# 16SegBoard_AutoRoute.net
KiCad netlist of a schematic drawn in EAGLE
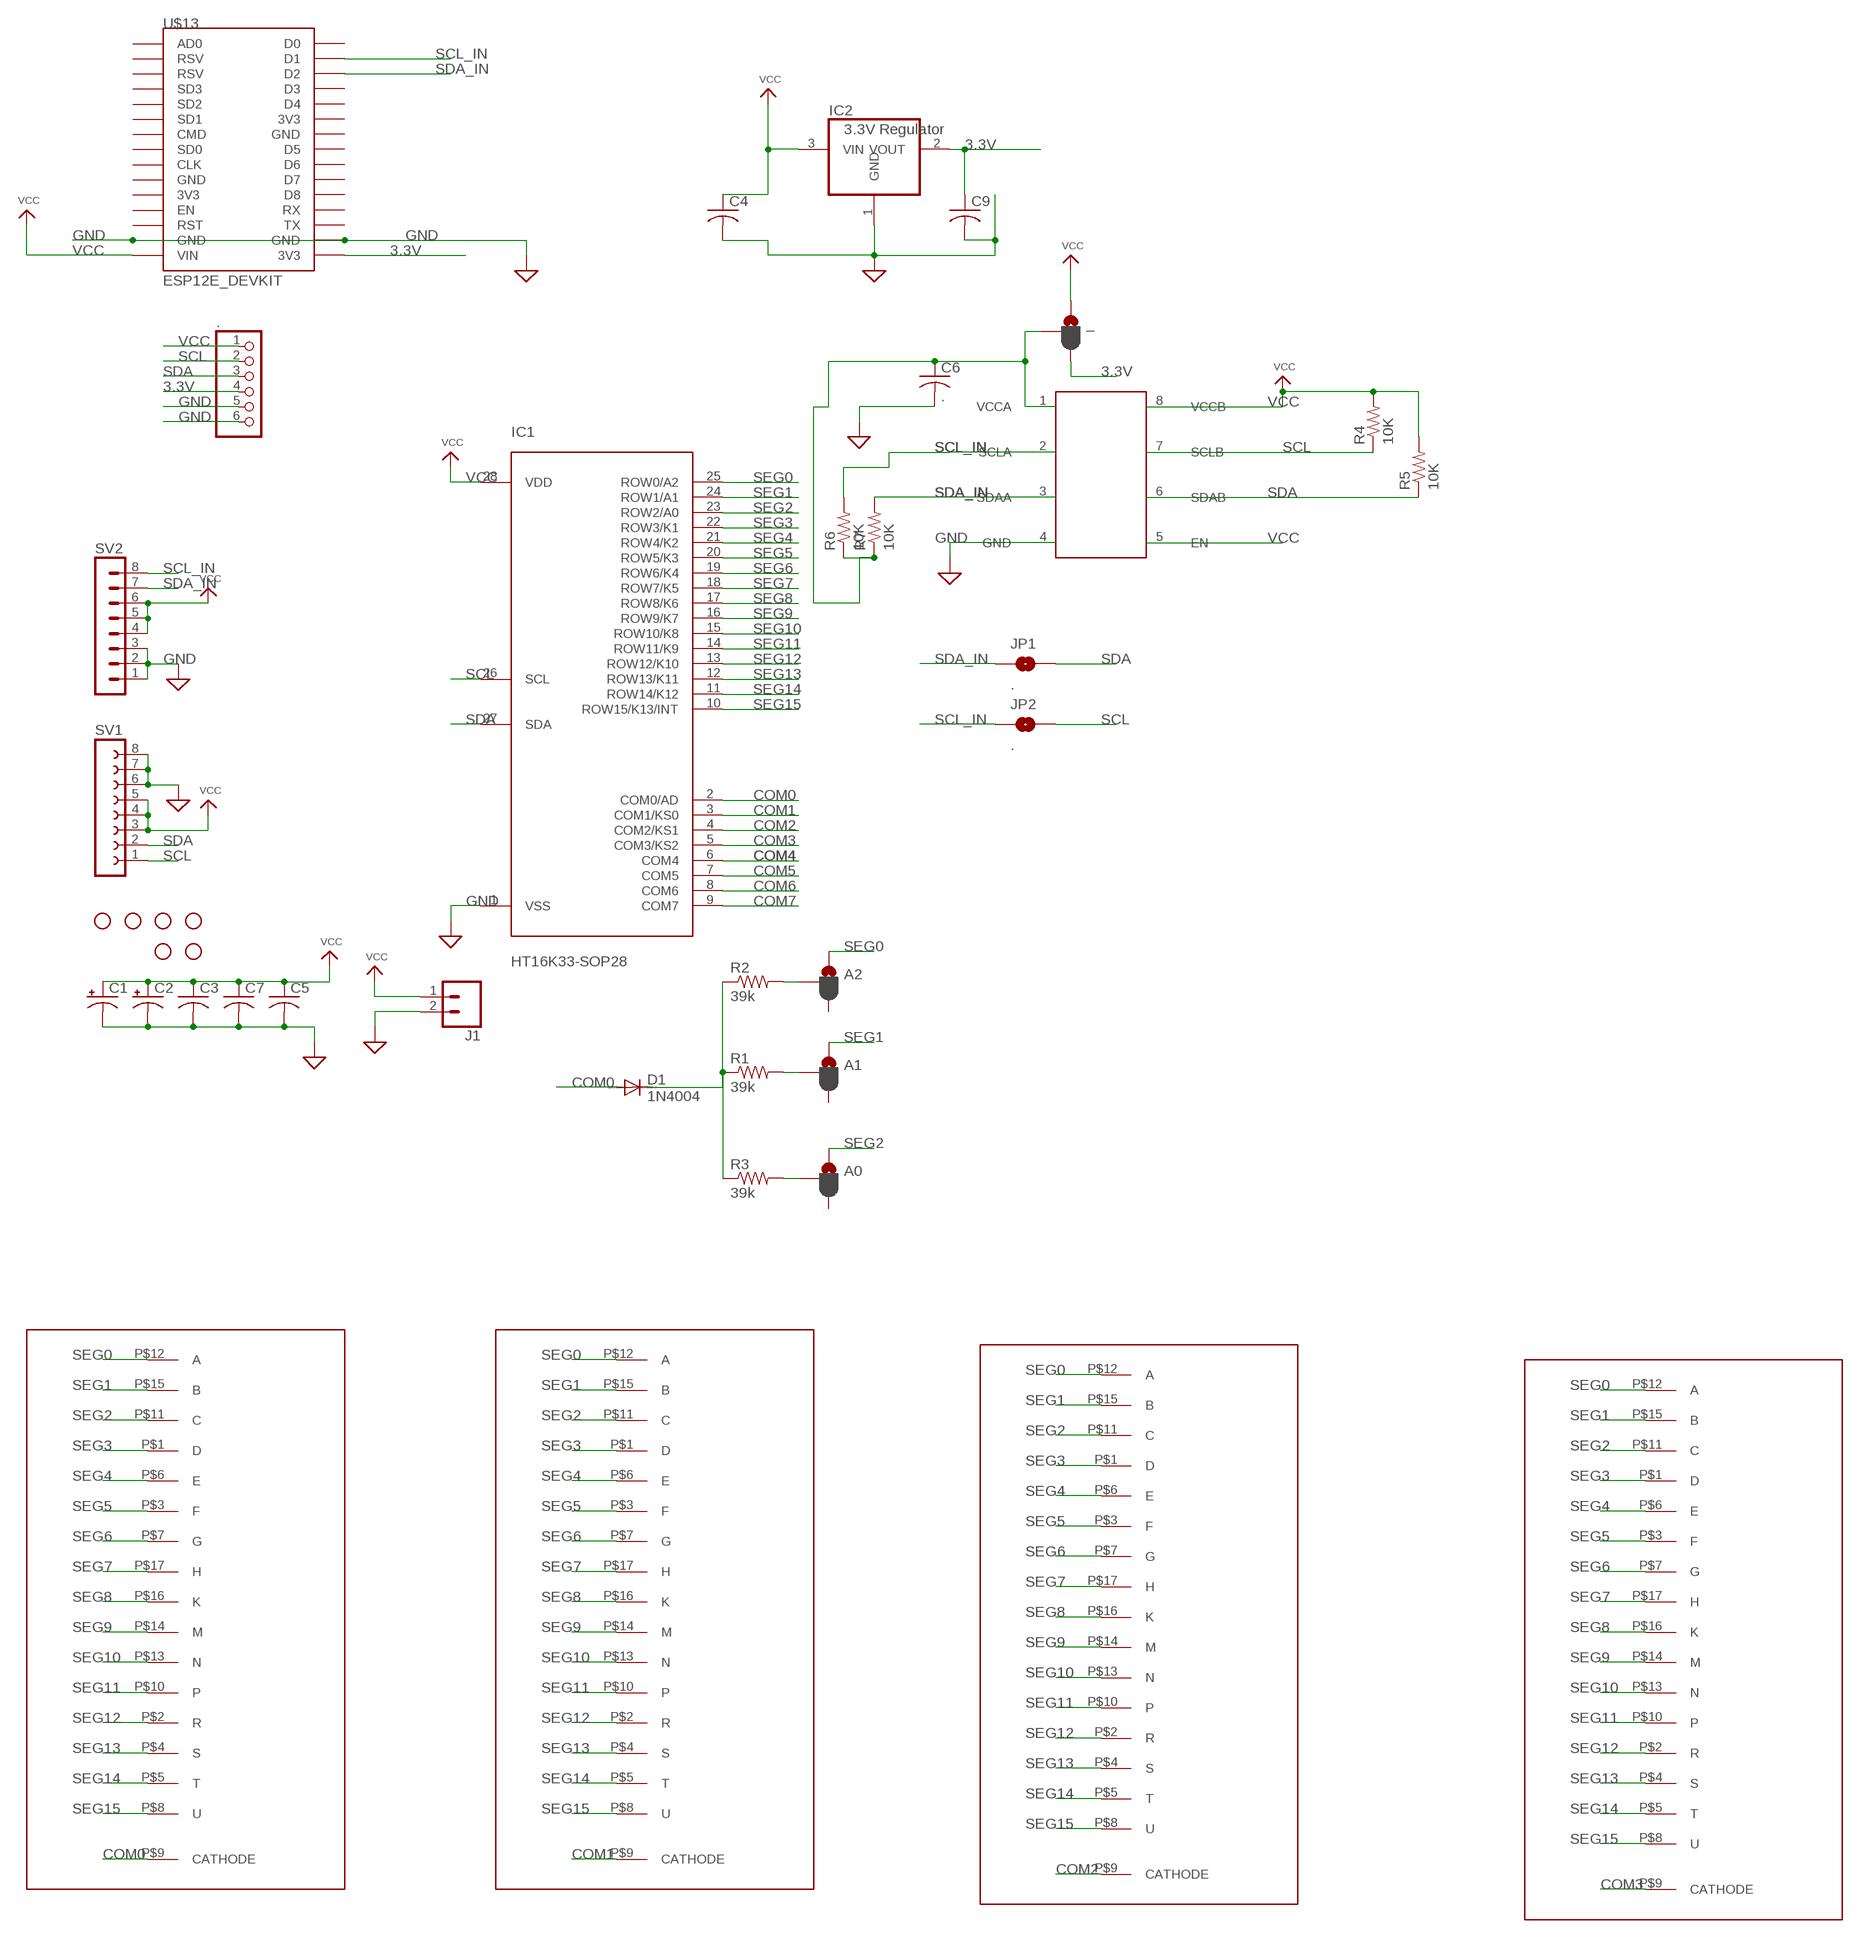
[diagram p0: schematic, sheet 1, part 1 of 2]
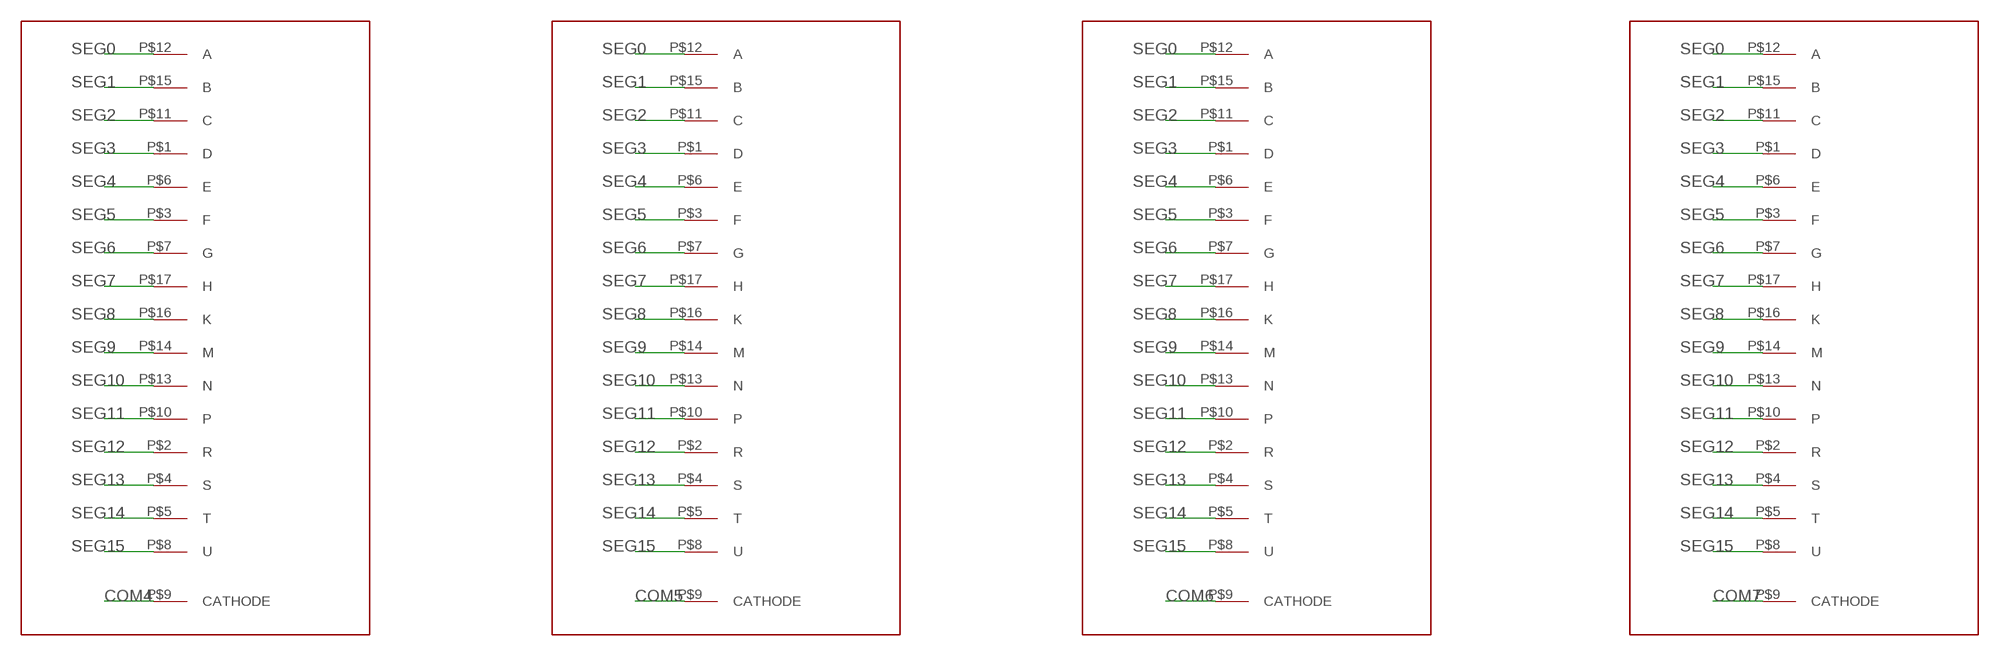
[diagram p1: schematic, sheet 1, part 2 of 2]

(export (version "E")
  (design (tool "Eeschema 10.0.6"))
  (components
    (comp (ref ".")
      (value "PINHD-1X6")
      (footprint "eagle-import:1X06")
      (libsource (lib "eagle-import") (part "PINHD-1X6"))
    )
    (comp (ref "A0")
      (value "JUMPER-SMT_3_1-NC_PASTE_SILK")
      (footprint "eagle-import:SMT-JUMPER_3_1-NC_PASTE_SILK")
      (libsource (lib "eagle-import") (part "JUMPER-SMT_3_1-NC_PASTE_SILK"))
    )
    (comp (ref "A1")
      (value "JUMPER-SMT_3_1-NC_PASTE_SILK")
      (footprint "eagle-import:SMT-JUMPER_3_1-NC_PASTE_SILK")
      (libsource (lib "eagle-import") (part "JUMPER-SMT_3_1-NC_PASTE_SILK"))
    )
    (comp (ref "A2")
      (value "JUMPER-SMT_3_1-NC_PASTE_SILK")
      (footprint "eagle-import:SMT-JUMPER_3_1-NC_PASTE_SILK")
      (libsource (lib "eagle-import") (part "JUMPER-SMT_3_1-NC_PASTE_SILK"))
    )
    (comp (ref "C1")
      (value "CPOL-USE2.5-6")
      (footprint "eagle-import:E2,5-6")
      (libsource (lib "eagle-import") (part "CPOL-USE2.5-6"))
    )
    (comp (ref "C2")
      (value "CPOL-USE2.5-6")
      (footprint "eagle-import:E2,5-6")
      (libsource (lib "eagle-import") (part "CPOL-USE2.5-6"))
    )
    (comp (ref "C3")
      (value "C-USC0805")
      (footprint "eagle-import:C0805")
      (libsource (lib "eagle-import") (part "C-USC0805"))
    )
    (comp (ref "C4")
      (value "C-USC0805")
      (footprint "eagle-import:C0805")
      (libsource (lib "eagle-import") (part "C-USC0805"))
    )
    (comp (ref "C5")
      (value "C-US025-030X050")
      (footprint "eagle-import:C025-030X050")
      (libsource (lib "eagle-import") (part "C-US025-030X050"))
    )
    (comp (ref "C6")
      (value ".")
      (footprint "eagle-import:C0805")
      (libsource (lib "eagle-import") (part "C-USC0805"))
    )
    (comp (ref "C7")
      (value "C-USC0805")
      (footprint "eagle-import:C0805")
      (libsource (lib "eagle-import") (part "C-USC0805"))
    )
    (comp (ref "C9")
      (value "C-USC0805")
      (footprint "eagle-import:C0805")
      (libsource (lib "eagle-import") (part "C-USC0805"))
    )
    (comp (ref "D1")
      (value "1N4004")
      (footprint "eagle-import:DO41-10")
      (libsource (lib "eagle-import") (part "1N4004"))
    )
    (comp (ref "H1")
      (value "STAND-OFF")
      (footprint "eagle-import:STAND-OFF")
      (libsource (lib "eagle-import") (part "STAND-OFF"))
    )
    (comp (ref "H2")
      (value "STAND-OFF")
      (footprint "eagle-import:STAND-OFF")
      (libsource (lib "eagle-import") (part "STAND-OFF"))
    )
    (comp (ref "H3")
      (value "STAND-OFF")
      (footprint "eagle-import:STAND-OFF")
      (libsource (lib "eagle-import") (part "STAND-OFF"))
    )
    (comp (ref "H4")
      (value "STAND-OFF")
      (footprint "eagle-import:STAND-OFF")
      (libsource (lib "eagle-import") (part "STAND-OFF"))
    )
    (comp (ref "H5")
      (value "STAND-OFF")
      (footprint "eagle-import:STAND-OFF")
      (libsource (lib "eagle-import") (part "STAND-OFF"))
    )
    (comp (ref "H6")
      (value "STAND-OFF")
      (footprint "eagle-import:STAND-OFF")
      (libsource (lib "eagle-import") (part "STAND-OFF"))
    )
    (comp (ref "IC1")
      (value "HT16K33-SOP28")
      (footprint "eagle-import:SOIC127P1031X264-28N")
      (libsource (lib "eagle-import") (part "HT16K33-SOP28"))
    )
    (comp (ref "IC2")
      (value "3.3V Regulator")
      (footprint "eagle-import:SOT223")
      (fields (field (name "MPN") "REG1117"))
      (libsource (lib "eagle-import") (part "REG1117"))
    )
    (comp (ref "J1")
      (value "CONN_025MM")
      (footprint "eagle-import:SCREWTERMINAL-5MM-2")
      (libsource (lib "eagle-import") (part "CONN_025MM"))
    )
    (comp (ref "JP1")
      (value ".")
      (footprint "eagle-import:SMT-JUMPER_2_NO_NO-SILK")
      (libsource (lib "eagle-import") (part "JUMPER-SMT_2_NO_NO-SILK"))
    )
    (comp (ref "JP2")
      (value ".")
      (footprint "eagle-import:SMT-JUMPER_2_NO_NO-SILK")
      (libsource (lib "eagle-import") (part "JUMPER-SMT_2_NO_NO-SILK"))
    )
    (comp (ref "R1")
      (value "39k")
      (footprint "eagle-import:M1206")
      (libsource (lib "eagle-import") (part "R-US_M1206"))
    )
    (comp (ref "R2")
      (value "39k")
      (footprint "eagle-import:M1206")
      (libsource (lib "eagle-import") (part "R-US_M1206"))
    )
    (comp (ref "R3")
      (value "39k")
      (footprint "eagle-import:M1206")
      (libsource (lib "eagle-import") (part "R-US_M1206"))
    )
    (comp (ref "R4")
      (value "10K")
      (footprint "eagle-import:R1206")
      (libsource (lib "eagle-import") (part "R-US_R1206"))
    )
    (comp (ref "R5")
      (value "10K")
      (footprint "eagle-import:R1206")
      (libsource (lib "eagle-import") (part "R-US_R1206"))
    )
    (comp (ref "R6")
      (value "10K")
      (footprint "eagle-import:R1206")
      (libsource (lib "eagle-import") (part "R-US_R1206"))
    )
    (comp (ref "R7")
      (value "10K")
      (footprint "eagle-import:R1206")
      (libsource (lib "eagle-import") (part "R-US_R1206"))
    )
    (comp (ref "SV1")
      (value "FE08W")
      (footprint "eagle-import:FE08W")
      (libsource (lib "eagle-import") (part "FE08W"))
    )
    (comp (ref "SV2")
      (value "MA08-1W")
      (footprint "eagle-import:MA08-1W")
      (libsource (lib "eagle-import") (part "MA08-1W"))
    )
    (comp (ref "TCA9517")
      (value "TCA9517")
      (footprint "eagle-import:SOIC-8")
      (libsource (lib "eagle-import") (part "TCA9517"))
    )
    (comp (ref "U$1")
      (value "16SEG")
      (footprint "eagle-import:16SEGLARGE_PKG")
      (libsource (lib "eagle-import") (part "16SEG"))
    )
    (comp (ref "U$2")
      (value "16SEG")
      (footprint "eagle-import:16SEGLARGE_PKG")
      (libsource (lib "eagle-import") (part "16SEG"))
    )
    (comp (ref "U$3")
      (value "16SEG")
      (footprint "eagle-import:16SEGLARGE_PKG")
      (libsource (lib "eagle-import") (part "16SEG"))
    )
    (comp (ref "U$4")
      (value "16SEG")
      (footprint "eagle-import:16SEGLARGE_PKG")
      (libsource (lib "eagle-import") (part "16SEG"))
    )
    (comp (ref "U$5")
      (value "16SEG")
      (footprint "eagle-import:16SEGLARGE_PKG")
      (libsource (lib "eagle-import") (part "16SEG"))
    )
    (comp (ref "U$6")
      (value "16SEG")
      (footprint "eagle-import:16SEGLARGE_PKG")
      (libsource (lib "eagle-import") (part "16SEG"))
    )
    (comp (ref "U$7")
      (value "16SEG")
      (footprint "eagle-import:16SEGLARGE_PKG")
      (libsource (lib "eagle-import") (part "16SEG"))
    )
    (comp (ref "U$8")
      (value "16SEG")
      (footprint "eagle-import:16SEGLARGE_PKG")
      (libsource (lib "eagle-import") (part "16SEG"))
    )
    (comp (ref "U$13")
      (value "ESP12E_DEVKIT")
      (footprint "eagle-import:ESP12E_DEVKIT")
      (libsource (lib "eagle-import") (part "ESP12E_DEVKIT"))
    )
    (comp (ref "_")
      (value "JUMPER-SMT_3_1-NC_PASTE_SILK")
      (footprint "eagle-import:SMT-JUMPER_3_1-NC_PASTE_SILK")
      (libsource (lib "eagle-import") (part "JUMPER-SMT_3_1-NC_PASTE_SILK"))
    )
  )
  (nets
    (net (code "1") (name "/3.3V") (class "Default")
      (node (ref ".") (pin "4") (pinfunction "4_4") (pintype "passive"))
      (node (ref "C9") (pin "1") (pinfunction "1_1") (pintype "passive"))
      (node (ref "IC2") (pin "2") (pinfunction "VOUT_2") (pintype "output"))
      (node (ref "U$13") (pin "3V3@2") (pinfunction "3V3_3V3@2") (pintype "bidirectional"))
      (node (ref "_") (pin "3") (pinfunction "3_3") (pintype "passive"))
    )
    (net (code "2") (name "/COM0") (class "Default")
      (node (ref "D1") (pin "A") (pinfunction "A_A") (pintype "passive"))
      (node (ref "IC1") (pin "2") (pinfunction "COM0/AD_2") (pintype "output"))
      (node (ref "U$1") (pin "P$9") (pinfunction "CATHODE_P$9") (pintype "bidirectional"))
    )
    (net (code "3") (name "/COM1") (class "Default")
      (node (ref "IC1") (pin "3") (pinfunction "COM1/KS0_3") (pintype "output"))
      (node (ref "U$2") (pin "P$9") (pinfunction "CATHODE_P$9") (pintype "bidirectional"))
    )
    (net (code "4") (name "/COM2") (class "Default")
      (node (ref "IC1") (pin "4") (pinfunction "COM2/KS1_4") (pintype "output"))
      (node (ref "U$3") (pin "P$9") (pinfunction "CATHODE_P$9") (pintype "bidirectional"))
    )
    (net (code "5") (name "/COM3") (class "Default")
      (node (ref "IC1") (pin "5") (pinfunction "COM3/KS2_5") (pintype "output"))
      (node (ref "U$4") (pin "P$9") (pinfunction "CATHODE_P$9") (pintype "bidirectional"))
    )
    (net (code "6") (name "/COM4") (class "Default")
      (node (ref "IC1") (pin "6") (pinfunction "COM4_6") (pintype "output"))
      (node (ref "U$5") (pin "P$9") (pinfunction "CATHODE_P$9") (pintype "bidirectional"))
    )
    (net (code "7") (name "/COM5") (class "Default")
      (node (ref "IC1") (pin "7") (pinfunction "COM5_7") (pintype "output"))
      (node (ref "U$6") (pin "P$9") (pinfunction "CATHODE_P$9") (pintype "bidirectional"))
    )
    (net (code "8") (name "/COM6") (class "Default")
      (node (ref "IC1") (pin "8") (pinfunction "COM6_8") (pintype "output"))
      (node (ref "U$7") (pin "P$9") (pinfunction "CATHODE_P$9") (pintype "bidirectional"))
    )
    (net (code "9") (name "/COM7") (class "Default")
      (node (ref "IC1") (pin "9") (pinfunction "COM7_9") (pintype "output"))
      (node (ref "U$8") (pin "P$9") (pinfunction "CATHODE_P$9") (pintype "bidirectional"))
    )
    (net (code "10") (name "/SCL") (class "Default")
      (node (ref ".") (pin "2") (pinfunction "2_2") (pintype "passive"))
      (node (ref "IC1") (pin "26") (pinfunction "SCL_26") (pintype "input"))
      (node (ref "JP2") (pin "2") (pinfunction "2_2") (pintype "passive"))
      (node (ref "R4") (pin "1") (pinfunction "1_1") (pintype "passive"))
      (node (ref "SV1") (pin "1") (pinfunction "1_1") (pintype "passive"))
      (node (ref "TCA9517") (pin "7") (pinfunction "SCLB_7") (pintype "bidirectional"))
    )
    (net (code "11") (name "/SCL_IN") (class "Default")
      (node (ref "JP2") (pin "1") (pinfunction "1_1") (pintype "passive"))
      (node (ref "R6") (pin "2") (pinfunction "2_2") (pintype "passive"))
      (node (ref "SV2") (pin "8") (pinfunction "8_8") (pintype "passive"))
      (node (ref "TCA9517") (pin "2") (pinfunction "SCLA_2") (pintype "bidirectional"))
      (node (ref "U$13") (pin "D1") (pinfunction "D1_D1") (pintype "bidirectional"))
    )
    (net (code "12") (name "/SDA") (class "Default")
      (node (ref ".") (pin "3") (pinfunction "3_3") (pintype "passive"))
      (node (ref "IC1") (pin "27") (pinfunction "SDA_27") (pintype "bidirectional"))
      (node (ref "JP1") (pin "2") (pinfunction "2_2") (pintype "passive"))
      (node (ref "R5") (pin "1") (pinfunction "1_1") (pintype "passive"))
      (node (ref "SV1") (pin "2") (pinfunction "2_2") (pintype "passive"))
      (node (ref "TCA9517") (pin "6") (pinfunction "SDAB_6") (pintype "bidirectional"))
    )
    (net (code "13") (name "/SDA_IN") (class "Default")
      (node (ref "JP1") (pin "1") (pinfunction "1_1") (pintype "passive"))
      (node (ref "R7") (pin "2") (pinfunction "2_2") (pintype "passive"))
      (node (ref "SV2") (pin "7") (pinfunction "7_7") (pintype "passive"))
      (node (ref "TCA9517") (pin "3") (pinfunction "SDAA_3") (pintype "bidirectional"))
      (node (ref "U$13") (pin "D2") (pinfunction "D2_D2") (pintype "bidirectional"))
    )
    (net (code "14") (name "/SEG0") (class "Default")
      (node (ref "A2") (pin "1") (pinfunction "1_1") (pintype "passive"))
      (node (ref "IC1") (pin "25") (pinfunction "ROW0/A2_25") (pintype "bidirectional"))
      (node (ref "U$1") (pin "P$12") (pinfunction "A_P$12") (pintype "bidirectional"))
      (node (ref "U$2") (pin "P$12") (pinfunction "A_P$12") (pintype "bidirectional"))
      (node (ref "U$3") (pin "P$12") (pinfunction "A_P$12") (pintype "bidirectional"))
      (node (ref "U$4") (pin "P$12") (pinfunction "A_P$12") (pintype "bidirectional"))
      (node (ref "U$5") (pin "P$12") (pinfunction "A_P$12") (pintype "bidirectional"))
      (node (ref "U$6") (pin "P$12") (pinfunction "A_P$12") (pintype "bidirectional"))
      (node (ref "U$7") (pin "P$12") (pinfunction "A_P$12") (pintype "bidirectional"))
      (node (ref "U$8") (pin "P$12") (pinfunction "A_P$12") (pintype "bidirectional"))
    )
    (net (code "15") (name "/SEG1") (class "Default")
      (node (ref "A1") (pin "1") (pinfunction "1_1") (pintype "passive"))
      (node (ref "IC1") (pin "24") (pinfunction "ROW1/A1_24") (pintype "bidirectional"))
      (node (ref "U$1") (pin "P$15") (pinfunction "B_P$15") (pintype "bidirectional"))
      (node (ref "U$2") (pin "P$15") (pinfunction "B_P$15") (pintype "bidirectional"))
      (node (ref "U$3") (pin "P$15") (pinfunction "B_P$15") (pintype "bidirectional"))
      (node (ref "U$4") (pin "P$15") (pinfunction "B_P$15") (pintype "bidirectional"))
      (node (ref "U$5") (pin "P$15") (pinfunction "B_P$15") (pintype "bidirectional"))
      (node (ref "U$6") (pin "P$15") (pinfunction "B_P$15") (pintype "bidirectional"))
      (node (ref "U$7") (pin "P$15") (pinfunction "B_P$15") (pintype "bidirectional"))
      (node (ref "U$8") (pin "P$15") (pinfunction "B_P$15") (pintype "bidirectional"))
    )
    (net (code "16") (name "/SEG2") (class "Default")
      (node (ref "A0") (pin "1") (pinfunction "1_1") (pintype "passive"))
      (node (ref "IC1") (pin "23") (pinfunction "ROW2/A0_23") (pintype "bidirectional"))
      (node (ref "U$1") (pin "P$11") (pinfunction "C_P$11") (pintype "bidirectional"))
      (node (ref "U$2") (pin "P$11") (pinfunction "C_P$11") (pintype "bidirectional"))
      (node (ref "U$3") (pin "P$11") (pinfunction "C_P$11") (pintype "bidirectional"))
      (node (ref "U$4") (pin "P$11") (pinfunction "C_P$11") (pintype "bidirectional"))
      (node (ref "U$5") (pin "P$11") (pinfunction "C_P$11") (pintype "bidirectional"))
      (node (ref "U$6") (pin "P$11") (pinfunction "C_P$11") (pintype "bidirectional"))
      (node (ref "U$7") (pin "P$11") (pinfunction "C_P$11") (pintype "bidirectional"))
      (node (ref "U$8") (pin "P$11") (pinfunction "C_P$11") (pintype "bidirectional"))
    )
    (net (code "17") (name "/SEG3") (class "Default")
      (node (ref "IC1") (pin "22") (pinfunction "ROW3/K1_22") (pintype "bidirectional"))
      (node (ref "U$1") (pin "P$1") (pinfunction "D_P$1") (pintype "bidirectional"))
      (node (ref "U$2") (pin "P$1") (pinfunction "D_P$1") (pintype "bidirectional"))
      (node (ref "U$3") (pin "P$1") (pinfunction "D_P$1") (pintype "bidirectional"))
      (node (ref "U$4") (pin "P$1") (pinfunction "D_P$1") (pintype "bidirectional"))
      (node (ref "U$5") (pin "P$1") (pinfunction "D_P$1") (pintype "bidirectional"))
      (node (ref "U$6") (pin "P$1") (pinfunction "D_P$1") (pintype "bidirectional"))
      (node (ref "U$7") (pin "P$1") (pinfunction "D_P$1") (pintype "bidirectional"))
      (node (ref "U$8") (pin "P$1") (pinfunction "D_P$1") (pintype "bidirectional"))
    )
    (net (code "18") (name "/SEG4") (class "Default")
      (node (ref "IC1") (pin "21") (pinfunction "ROW4/K2_21") (pintype "bidirectional"))
      (node (ref "U$1") (pin "P$6") (pinfunction "E_P$6") (pintype "bidirectional"))
      (node (ref "U$2") (pin "P$6") (pinfunction "E_P$6") (pintype "bidirectional"))
      (node (ref "U$3") (pin "P$6") (pinfunction "E_P$6") (pintype "bidirectional"))
      (node (ref "U$4") (pin "P$6") (pinfunction "E_P$6") (pintype "bidirectional"))
      (node (ref "U$5") (pin "P$6") (pinfunction "E_P$6") (pintype "bidirectional"))
      (node (ref "U$6") (pin "P$6") (pinfunction "E_P$6") (pintype "bidirectional"))
      (node (ref "U$7") (pin "P$6") (pinfunction "E_P$6") (pintype "bidirectional"))
      (node (ref "U$8") (pin "P$6") (pinfunction "E_P$6") (pintype "bidirectional"))
    )
    (net (code "19") (name "/SEG5") (class "Default")
      (node (ref "IC1") (pin "20") (pinfunction "ROW5/K3_20") (pintype "bidirectional"))
      (node (ref "U$1") (pin "P$3") (pinfunction "F_P$3") (pintype "bidirectional"))
      (node (ref "U$2") (pin "P$3") (pinfunction "F_P$3") (pintype "bidirectional"))
      (node (ref "U$3") (pin "P$3") (pinfunction "F_P$3") (pintype "bidirectional"))
      (node (ref "U$4") (pin "P$3") (pinfunction "F_P$3") (pintype "bidirectional"))
      (node (ref "U$5") (pin "P$3") (pinfunction "F_P$3") (pintype "bidirectional"))
      (node (ref "U$6") (pin "P$3") (pinfunction "F_P$3") (pintype "bidirectional"))
      (node (ref "U$7") (pin "P$3") (pinfunction "F_P$3") (pintype "bidirectional"))
      (node (ref "U$8") (pin "P$3") (pinfunction "F_P$3") (pintype "bidirectional"))
    )
    (net (code "20") (name "/SEG6") (class "Default")
      (node (ref "IC1") (pin "19") (pinfunction "ROW6/K4_19") (pintype "bidirectional"))
      (node (ref "U$1") (pin "P$7") (pinfunction "G_P$7") (pintype "bidirectional"))
      (node (ref "U$2") (pin "P$7") (pinfunction "G_P$7") (pintype "bidirectional"))
      (node (ref "U$3") (pin "P$7") (pinfunction "G_P$7") (pintype "bidirectional"))
      (node (ref "U$4") (pin "P$7") (pinfunction "G_P$7") (pintype "bidirectional"))
      (node (ref "U$5") (pin "P$7") (pinfunction "G_P$7") (pintype "bidirectional"))
      (node (ref "U$6") (pin "P$7") (pinfunction "G_P$7") (pintype "bidirectional"))
      (node (ref "U$7") (pin "P$7") (pinfunction "G_P$7") (pintype "bidirectional"))
      (node (ref "U$8") (pin "P$7") (pinfunction "G_P$7") (pintype "bidirectional"))
    )
    (net (code "21") (name "/SEG7") (class "Default")
      (node (ref "IC1") (pin "18") (pinfunction "ROW7/K5_18") (pintype "bidirectional"))
      (node (ref "U$1") (pin "P$17") (pinfunction "H_P$17") (pintype "bidirectional"))
      (node (ref "U$2") (pin "P$17") (pinfunction "H_P$17") (pintype "bidirectional"))
      (node (ref "U$3") (pin "P$17") (pinfunction "H_P$17") (pintype "bidirectional"))
      (node (ref "U$4") (pin "P$17") (pinfunction "H_P$17") (pintype "bidirectional"))
      (node (ref "U$5") (pin "P$17") (pinfunction "H_P$17") (pintype "bidirectional"))
      (node (ref "U$6") (pin "P$17") (pinfunction "H_P$17") (pintype "bidirectional"))
      (node (ref "U$7") (pin "P$17") (pinfunction "H_P$17") (pintype "bidirectional"))
      (node (ref "U$8") (pin "P$17") (pinfunction "H_P$17") (pintype "bidirectional"))
    )
    (net (code "22") (name "/SEG8") (class "Default")
      (node (ref "IC1") (pin "17") (pinfunction "ROW8/K6_17") (pintype "bidirectional"))
      (node (ref "U$1") (pin "P$16") (pinfunction "K_P$16") (pintype "bidirectional"))
      (node (ref "U$2") (pin "P$16") (pinfunction "K_P$16") (pintype "bidirectional"))
      (node (ref "U$3") (pin "P$16") (pinfunction "K_P$16") (pintype "bidirectional"))
      (node (ref "U$4") (pin "P$16") (pinfunction "K_P$16") (pintype "bidirectional"))
      (node (ref "U$5") (pin "P$16") (pinfunction "K_P$16") (pintype "bidirectional"))
      (node (ref "U$6") (pin "P$16") (pinfunction "K_P$16") (pintype "bidirectional"))
      (node (ref "U$7") (pin "P$16") (pinfunction "K_P$16") (pintype "bidirectional"))
      (node (ref "U$8") (pin "P$16") (pinfunction "K_P$16") (pintype "bidirectional"))
    )
    (net (code "23") (name "/SEG9") (class "Default")
      (node (ref "IC1") (pin "16") (pinfunction "ROW9/K7_16") (pintype "bidirectional"))
      (node (ref "U$1") (pin "P$14") (pinfunction "M_P$14") (pintype "bidirectional"))
      (node (ref "U$2") (pin "P$14") (pinfunction "M_P$14") (pintype "bidirectional"))
      (node (ref "U$3") (pin "P$14") (pinfunction "M_P$14") (pintype "bidirectional"))
      (node (ref "U$4") (pin "P$14") (pinfunction "M_P$14") (pintype "bidirectional"))
      (node (ref "U$5") (pin "P$14") (pinfunction "M_P$14") (pintype "bidirectional"))
      (node (ref "U$6") (pin "P$14") (pinfunction "M_P$14") (pintype "bidirectional"))
      (node (ref "U$7") (pin "P$14") (pinfunction "M_P$14") (pintype "bidirectional"))
      (node (ref "U$8") (pin "P$14") (pinfunction "M_P$14") (pintype "bidirectional"))
    )
    (net (code "24") (name "/SEG10") (class "Default")
      (node (ref "IC1") (pin "15") (pinfunction "ROW10/K8_15") (pintype "bidirectional"))
      (node (ref "U$1") (pin "P$13") (pinfunction "N_P$13") (pintype "bidirectional"))
      (node (ref "U$2") (pin "P$13") (pinfunction "N_P$13") (pintype "bidirectional"))
      (node (ref "U$3") (pin "P$13") (pinfunction "N_P$13") (pintype "bidirectional"))
      (node (ref "U$4") (pin "P$13") (pinfunction "N_P$13") (pintype "bidirectional"))
      (node (ref "U$5") (pin "P$13") (pinfunction "N_P$13") (pintype "bidirectional"))
      (node (ref "U$6") (pin "P$13") (pinfunction "N_P$13") (pintype "bidirectional"))
      (node (ref "U$7") (pin "P$13") (pinfunction "N_P$13") (pintype "bidirectional"))
      (node (ref "U$8") (pin "P$13") (pinfunction "N_P$13") (pintype "bidirectional"))
    )
    (net (code "25") (name "/SEG11") (class "Default")
      (node (ref "IC1") (pin "14") (pinfunction "ROW11/K9_14") (pintype "bidirectional"))
      (node (ref "U$1") (pin "P$10") (pinfunction "P_P$10") (pintype "bidirectional"))
      (node (ref "U$2") (pin "P$10") (pinfunction "P_P$10") (pintype "bidirectional"))
      (node (ref "U$3") (pin "P$10") (pinfunction "P_P$10") (pintype "bidirectional"))
      (node (ref "U$4") (pin "P$10") (pinfunction "P_P$10") (pintype "bidirectional"))
      (node (ref "U$5") (pin "P$10") (pinfunction "P_P$10") (pintype "bidirectional"))
      (node (ref "U$6") (pin "P$10") (pinfunction "P_P$10") (pintype "bidirectional"))
      (node (ref "U$7") (pin "P$10") (pinfunction "P_P$10") (pintype "bidirectional"))
      (node (ref "U$8") (pin "P$10") (pinfunction "P_P$10") (pintype "bidirectional"))
    )
    (net (code "26") (name "/SEG12") (class "Default")
      (node (ref "IC1") (pin "13") (pinfunction "ROW12/K10_13") (pintype "bidirectional"))
      (node (ref "U$1") (pin "P$2") (pinfunction "R_P$2") (pintype "bidirectional"))
      (node (ref "U$2") (pin "P$2") (pinfunction "R_P$2") (pintype "bidirectional"))
      (node (ref "U$3") (pin "P$2") (pinfunction "R_P$2") (pintype "bidirectional"))
      (node (ref "U$4") (pin "P$2") (pinfunction "R_P$2") (pintype "bidirectional"))
      (node (ref "U$5") (pin "P$2") (pinfunction "R_P$2") (pintype "bidirectional"))
      (node (ref "U$6") (pin "P$2") (pinfunction "R_P$2") (pintype "bidirectional"))
      (node (ref "U$7") (pin "P$2") (pinfunction "R_P$2") (pintype "bidirectional"))
      (node (ref "U$8") (pin "P$2") (pinfunction "R_P$2") (pintype "bidirectional"))
    )
    (net (code "27") (name "/SEG13") (class "Default")
      (node (ref "IC1") (pin "12") (pinfunction "ROW13/K11_12") (pintype "bidirectional"))
      (node (ref "U$1") (pin "P$4") (pinfunction "S_P$4") (pintype "bidirectional"))
      (node (ref "U$2") (pin "P$4") (pinfunction "S_P$4") (pintype "bidirectional"))
      (node (ref "U$3") (pin "P$4") (pinfunction "S_P$4") (pintype "bidirectional"))
      (node (ref "U$4") (pin "P$4") (pinfunction "S_P$4") (pintype "bidirectional"))
      (node (ref "U$5") (pin "P$4") (pinfunction "S_P$4") (pintype "bidirectional"))
      (node (ref "U$6") (pin "P$4") (pinfunction "S_P$4") (pintype "bidirectional"))
      (node (ref "U$7") (pin "P$4") (pinfunction "S_P$4") (pintype "bidirectional"))
      (node (ref "U$8") (pin "P$4") (pinfunction "S_P$4") (pintype "bidirectional"))
    )
    (net (code "28") (name "/SEG14") (class "Default")
      (node (ref "IC1") (pin "11") (pinfunction "ROW14/K12_11") (pintype "bidirectional"))
      (node (ref "U$1") (pin "P$5") (pinfunction "T_P$5") (pintype "bidirectional"))
      (node (ref "U$2") (pin "P$5") (pinfunction "T_P$5") (pintype "bidirectional"))
      (node (ref "U$3") (pin "P$5") (pinfunction "T_P$5") (pintype "bidirectional"))
      (node (ref "U$4") (pin "P$5") (pinfunction "T_P$5") (pintype "bidirectional"))
      (node (ref "U$5") (pin "P$5") (pinfunction "T_P$5") (pintype "bidirectional"))
      (node (ref "U$6") (pin "P$5") (pinfunction "T_P$5") (pintype "bidirectional"))
      (node (ref "U$7") (pin "P$5") (pinfunction "T_P$5") (pintype "bidirectional"))
      (node (ref "U$8") (pin "P$5") (pinfunction "T_P$5") (pintype "bidirectional"))
    )
    (net (code "29") (name "/SEG15") (class "Default")
      (node (ref "IC1") (pin "10") (pinfunction "ROW15/K13/INT_10") (pintype "bidirectional"))
      (node (ref "U$1") (pin "P$8") (pinfunction "U_P$8") (pintype "bidirectional"))
      (node (ref "U$2") (pin "P$8") (pinfunction "U_P$8") (pintype "bidirectional"))
      (node (ref "U$3") (pin "P$8") (pinfunction "U_P$8") (pintype "bidirectional"))
      (node (ref "U$4") (pin "P$8") (pinfunction "U_P$8") (pintype "bidirectional"))
      (node (ref "U$5") (pin "P$8") (pinfunction "U_P$8") (pintype "bidirectional"))
      (node (ref "U$6") (pin "P$8") (pinfunction "U_P$8") (pintype "bidirectional"))
      (node (ref "U$7") (pin "P$8") (pinfunction "U_P$8") (pintype "bidirectional"))
      (node (ref "U$8") (pin "P$8") (pinfunction "U_P$8") (pintype "bidirectional"))
    )
    (net (code "30") (name "Net-(A0-Pad2)") (class "Default")
      (node (ref "A0") (pin "2") (pinfunction "2_2") (pintype "passive"))
      (node (ref "R3") (pin "2") (pinfunction "2_2") (pintype "passive"))
    )
    (net (code "31") (name "Net-(A1-Pad2)") (class "Default")
      (node (ref "A1") (pin "2") (pinfunction "2_2") (pintype "passive"))
      (node (ref "R1") (pin "2") (pinfunction "2_2") (pintype "passive"))
    )
    (net (code "32") (name "Net-(A2-Pad2)") (class "Default")
      (node (ref "A2") (pin "2") (pinfunction "2_2") (pintype "passive"))
      (node (ref "R2") (pin "2") (pinfunction "2_2") (pintype "passive"))
    )
    (net (code "33") (name "Net-(D1-PadC)") (class "Default")
      (node (ref "D1") (pin "C") (pinfunction "C_C") (pintype "passive"))
      (node (ref "R1") (pin "1") (pinfunction "1_1") (pintype "passive"))
      (node (ref "R2") (pin "1") (pinfunction "1_1") (pintype "passive"))
      (node (ref "R3") (pin "1") (pinfunction "1_1") (pintype "passive"))
    )
    (net (code "34") (name "Net-(TCA9517-VCCA)") (class "Default")
      (node (ref "C6") (pin "1") (pinfunction "1_1") (pintype "passive"))
      (node (ref "R6") (pin "1") (pinfunction "1_1") (pintype "passive"))
      (node (ref "R7") (pin "1") (pinfunction "1_1") (pintype "passive"))
      (node (ref "TCA9517") (pin "1") (pinfunction "VCCA_1") (pintype "bidirectional"))
      (node (ref "_") (pin "2") (pinfunction "2_2") (pintype "passive"))
    )
    (net (code "35") (name "SUP") (class "Default")
      (node (ref ".") (pin "5") (pinfunction "5_5") (pintype "passive"))
      (node (ref ".") (pin "6") (pinfunction "6_6") (pintype "passive"))
      (node (ref "C1") (pin "-") (pinfunction "-_-") (pintype "passive"))
      (node (ref "C2") (pin "-") (pinfunction "-_-") (pintype "passive"))
      (node (ref "C3") (pin "2") (pinfunction "2_2") (pintype "passive"))
      (node (ref "C4") (pin "2") (pinfunction "2_2") (pintype "passive"))
      (node (ref "C5") (pin "2") (pinfunction "2_2") (pintype "passive"))
      (node (ref "C6") (pin "2") (pinfunction "2_2") (pintype "passive"))
      (node (ref "C7") (pin "2") (pinfunction "2_2") (pintype "passive"))
      (node (ref "C9") (pin "2") (pinfunction "2_2") (pintype "passive"))
      (node (ref "IC1") (pin "1") (pinfunction "VSS_1") (pintype "power_in"))
      (node (ref "IC2") (pin "1") (pinfunction "GND_1") (pintype "power_in"))
      (node (ref "J1") (pin "2") (pinfunction "2_2") (pintype "passive"))
      (node (ref "SV1") (pin "6") (pinfunction "6_6") (pintype "passive"))
      (node (ref "SV1") (pin "7") (pinfunction "7_7") (pintype "passive"))
      (node (ref "SV1") (pin "8") (pinfunction "8_8") (pintype "passive"))
      (node (ref "SV2") (pin "1") (pinfunction "1_1") (pintype "passive"))
      (node (ref "SV2") (pin "2") (pinfunction "2_2") (pintype "passive"))
      (node (ref "SV2") (pin "3") (pinfunction "3_3") (pintype "passive"))
      (node (ref "TCA9517") (pin "4") (pinfunction "GND_4") (pintype "bidirectional"))
      (node (ref "U$13") (pin "GND@1") (pinfunction "GND_GND@1") (pintype "bidirectional"))
      (node (ref "U$13") (pin "GND@3") (pinfunction "GND_GND@3") (pintype "bidirectional"))
    )
    (net (code "36") (name "VCC") (class "Default")
      (node (ref ".") (pin "1") (pinfunction "1_1") (pintype "passive"))
      (node (ref "C1") (pin "+") (pinfunction "+_+") (pintype "passive"))
      (node (ref "C2") (pin "+") (pinfunction "+_+") (pintype "passive"))
      (node (ref "C3") (pin "1") (pinfunction "1_1") (pintype "passive"))
      (node (ref "C4") (pin "1") (pinfunction "1_1") (pintype "passive"))
      (node (ref "C5") (pin "1") (pinfunction "1_1") (pintype "passive"))
      (node (ref "C7") (pin "1") (pinfunction "1_1") (pintype "passive"))
      (node (ref "IC1") (pin "28") (pinfunction "VDD_28") (pintype "power_in"))
      (node (ref "IC2") (pin "3") (pinfunction "VIN_3") (pintype "input"))
      (node (ref "J1") (pin "1") (pinfunction "1_1") (pintype "passive"))
      (node (ref "R4") (pin "2") (pinfunction "2_2") (pintype "passive"))
      (node (ref "R5") (pin "2") (pinfunction "2_2") (pintype "passive"))
      (node (ref "SV1") (pin "3") (pinfunction "3_3") (pintype "passive"))
      (node (ref "SV1") (pin "4") (pinfunction "4_4") (pintype "passive"))
      (node (ref "SV1") (pin "5") (pinfunction "5_5") (pintype "passive"))
      (node (ref "SV2") (pin "4") (pinfunction "4_4") (pintype "passive"))
      (node (ref "SV2") (pin "5") (pinfunction "5_5") (pintype "passive"))
      (node (ref "SV2") (pin "6") (pinfunction "6_6") (pintype "passive"))
      (node (ref "TCA9517") (pin "5") (pinfunction "EN_5") (pintype "bidirectional"))
      (node (ref "TCA9517") (pin "8") (pinfunction "VCCB_8") (pintype "bidirectional"))
      (node (ref "U$13") (pin "VIN") (pinfunction "VIN_VIN") (pintype "bidirectional"))
      (node (ref "_") (pin "1") (pinfunction "1_1") (pintype "passive"))
    )
    (net (code "37") (name "unconnected-(A0-Pad3)") (class "Default")
      (node (ref "A0") (pin "3") (pinfunction "3_3") (pintype "passive"))
    )
    (net (code "38") (name "unconnected-(A1-Pad3)") (class "Default")
      (node (ref "A1") (pin "3") (pinfunction "3_3") (pintype "passive"))
    )
    (net (code "39") (name "unconnected-(A2-Pad3)") (class "Default")
      (node (ref "A2") (pin "3") (pinfunction "3_3") (pintype "passive"))
    )
    (net (code "40") (name "unconnected-(U$13-3V3-Pad3V3@0)") (class "Default")
      (node (ref "U$13") (pin "3V3@0") (pinfunction "3V3_3V3@0") (pintype "bidirectional"))
    )
    (net (code "41") (name "unconnected-(U$13-3V3-Pad3V3@1)") (class "Default")
      (node (ref "U$13") (pin "3V3@1") (pinfunction "3V3_3V3@1") (pintype "bidirectional"))
    )
    (net (code "42") (name "unconnected-(U$13-GND-PadGND@0)") (class "Default")
      (node (ref "U$13") (pin "GND@0") (pinfunction "GND_GND@0") (pintype "bidirectional"))
    )
    (net (code "43") (name "unconnected-(U$13-GND-PadGND@2)") (class "Default")
      (node (ref "U$13") (pin "GND@2") (pinfunction "GND_GND@2") (pintype "bidirectional"))
    )
    (net (code "44") (name "unconnected-(U$13-PadAD0)") (class "Default")
      (node (ref "U$13") (pin "AD0") (pinfunction "AD0_AD0") (pintype "bidirectional"))
    )
    (net (code "45") (name "unconnected-(U$13-PadCLK)") (class "Default")
      (node (ref "U$13") (pin "CLK") (pinfunction "CLK_CLK") (pintype "bidirectional"))
    )
    (net (code "46") (name "unconnected-(U$13-PadCMD)") (class "Default")
      (node (ref "U$13") (pin "CMD") (pinfunction "CMD_CMD") (pintype "bidirectional"))
    )
    (net (code "47") (name "unconnected-(U$13-PadD0)") (class "Default")
      (node (ref "U$13") (pin "D0") (pinfunction "D0_D0") (pintype "bidirectional"))
    )
    (net (code "48") (name "unconnected-(U$13-PadD3)") (class "Default")
      (node (ref "U$13") (pin "D3") (pinfunction "D3_D3") (pintype "bidirectional"))
    )
    (net (code "49") (name "unconnected-(U$13-PadD4)") (class "Default")
      (node (ref "U$13") (pin "D4") (pinfunction "D4_D4") (pintype "bidirectional"))
    )
    (net (code "50") (name "unconnected-(U$13-PadD5)") (class "Default")
      (node (ref "U$13") (pin "D5") (pinfunction "D5_D5") (pintype "bidirectional"))
    )
    (net (code "51") (name "unconnected-(U$13-PadD6)") (class "Default")
      (node (ref "U$13") (pin "D6") (pinfunction "D6_D6") (pintype "bidirectional"))
    )
    (net (code "52") (name "unconnected-(U$13-PadD7)") (class "Default")
      (node (ref "U$13") (pin "D7") (pinfunction "D7_D7") (pintype "bidirectional"))
    )
    (net (code "53") (name "unconnected-(U$13-PadD8)") (class "Default")
      (node (ref "U$13") (pin "D8") (pinfunction "D8_D8") (pintype "bidirectional"))
    )
    (net (code "54") (name "unconnected-(U$13-PadEN)") (class "Default")
      (node (ref "U$13") (pin "EN") (pinfunction "EN_EN") (pintype "bidirectional"))
    )
    (net (code "55") (name "unconnected-(U$13-PadRST)") (class "Default")
      (node (ref "U$13") (pin "RST") (pinfunction "RST_RST") (pintype "bidirectional"))
    )
    (net (code "56") (name "unconnected-(U$13-PadRX)") (class "Default")
      (node (ref "U$13") (pin "RX") (pinfunction "RX_RX") (pintype "bidirectional"))
    )
    (net (code "57") (name "unconnected-(U$13-PadSD0)") (class "Default")
      (node (ref "U$13") (pin "SD0") (pinfunction "SD0_SD0") (pintype "bidirectional"))
    )
    (net (code "58") (name "unconnected-(U$13-PadSD1)") (class "Default")
      (node (ref "U$13") (pin "SD1") (pinfunction "SD1_SD1") (pintype "bidirectional"))
    )
    (net (code "59") (name "unconnected-(U$13-PadSD2)") (class "Default")
      (node (ref "U$13") (pin "SD2") (pinfunction "SD2_SD2") (pintype "bidirectional"))
    )
    (net (code "60") (name "unconnected-(U$13-PadSD3)") (class "Default")
      (node (ref "U$13") (pin "SD3") (pinfunction "SD3_SD3") (pintype "bidirectional"))
    )
    (net (code "61") (name "unconnected-(U$13-PadTX)") (class "Default")
      (node (ref "U$13") (pin "TX") (pinfunction "TX_TX") (pintype "bidirectional"))
    )
    (net (code "62") (name "unconnected-(U$13-RSV-PadRSV@0)") (class "Default")
      (node (ref "U$13") (pin "RSV@0") (pinfunction "RSV_RSV@0") (pintype "bidirectional"))
    )
    (net (code "63") (name "unconnected-(U$13-RSV-PadRSV@1)") (class "Default")
      (node (ref "U$13") (pin "RSV@1") (pinfunction "RSV_RSV@1") (pintype "bidirectional"))
    )
  )
)
